# Switches.net
KiCad netlist of a schematic drawn in Altium Designer
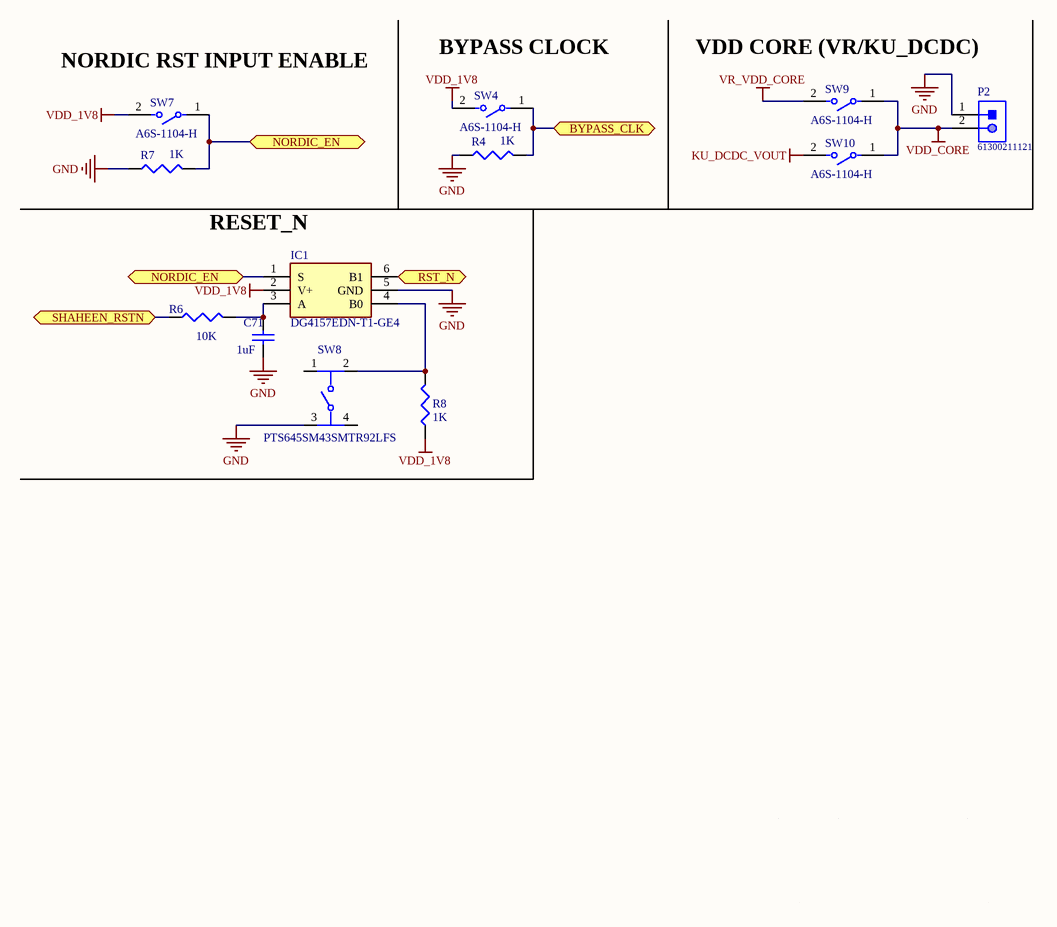
[diagram p0: Switches.SchDoc]

(export (version "E")
  (design (tool "Eeschema 10.0.6"))
  (components
    (comp (ref "C71")
      (value "1uF")
      (footprint "0603")
      (description "Capacitor")
      (fields (field (name "Comment") "Cap") (field (name "PUBLISHER") "Altium Limited"))
      (libsource (lib "Miscellaneous Devices") (part "Cap"))
    )
    (comp (ref "IC1")
      (value "DG4157EDN-T1-GE4")
      (footprint "SON35P100X100X38-6N")
      (description "Integrated Circuit")
      (fields (field (name "MOUSER2 PART NUMBER") "78-DG4157EDN-T1-GE4"))
      (libsource (lib "DG4157EDN-T1-GE4") (part "DG4157EDN-T1-GE4"))
    )
    (comp (ref "P2")
      (value "61300211121")
      (footprint "61300211121")
      (description "THT Vertical Pin Header WR-PHD, Pitch 2.54 mm, Single Row, 2 pins")
      (fields (field (name "MANUFACTURER") "Wurth Elektronik") (field (name "PUBLISHER") "WurthElektronik"))
      (libsource (lib "Altium Content Vault") (part "WE-CN-1P-M-R2"))
    )
    (comp (ref "R4")
      (value "1K")
      (footprint "J1-0603")
      (description "Resistor")
      (fields (field (name "Comment") "0R") (field (name "PUBLISHER") "Altium Limited"))
      (libsource (lib "Miscellaneous Devices") (part "Res3"))
    )
    (comp (ref "R6")
      (value "10K")
      (footprint "J1-0603")
      (description "Resistor")
      (fields (field (name "Comment") "0R") (field (name "PUBLISHER") "Altium Limited"))
      (libsource (lib "Miscellaneous Devices") (part "Res3"))
    )
    (comp (ref "R7")
      (value "1K")
      (footprint "J1-0603")
      (description "Resistor")
      (fields (field (name "Comment") "0R") (field (name "PUBLISHER") "Altium Limited"))
      (libsource (lib "Miscellaneous Devices") (part "Res3"))
    )
    (comp (ref "R8")
      (value "1K")
      (footprint "J1-0603")
      (description "Resistor")
      (fields (field (name "Comment") "0R") (field (name "PUBLISHER") "Altium Limited"))
      (libsource (lib "Miscellaneous Devices") (part "Res3"))
    )
    (comp (ref "SW4")
      (value "A6S-1104-H")
      (footprint "FP-A6S-1104-H-MFG")
      (description "SWITCH SLIDE DIP SPST 25MA 24V")
      (fields
        (field (name "MANUFACTURER") "Omron Electronics Inc-EMC Div")
        (field (name "OCTOPART") "https://octopart.com/a6s-1104-h-omron-55410938")
      )
      (libsource (lib "Altium Content Vault") (part "bb27bde45df87f1f469753f287ef5ae"))
    )
    (comp (ref "SW7")
      (value "A6S-1104-H")
      (footprint "FP-A6S-1104-H-MFG")
      (description "SWITCH SLIDE DIP SPST 25MA 24V")
      (fields
        (field (name "MANUFACTURER") "Omron Electronics Inc-EMC Div")
        (field (name "OCTOPART") "https://octopart.com/a6s-1104-h-omron-55410938")
      )
      (libsource (lib "Altium Content Vault") (part "bb27bde45df87f1f469753f287ef5ae"))
    )
    (comp (ref "SW8")
      (value "PTS645SM43SMTR92LFS")
      (footprint "FP-PTS645SM43SMTR92LFS-MFG")
      (description "SWITCH TACTILE SPST-NO 0.05A 12V")
      (libsource (lib "Altium Content Vault") (part "1adf0dd01260c80cf25a44bfd6b99ba"))
    )
    (comp (ref "SW9")
      (value "A6S-1104-H")
      (footprint "FP-A6S-1104-H-MFG")
      (description "SWITCH SLIDE DIP SPST 25MA 24V")
      (fields
        (field (name "MANUFACTURER") "Omron Electronics Inc-EMC Div")
        (field (name "OCTOPART") "https://octopart.com/a6s-1104-h-omron-55410938")
      )
      (libsource (lib "Altium Content Vault") (part "bb27bde45df87f1f469753f287ef5ae"))
    )
    (comp (ref "SW10")
      (value "A6S-1104-H")
      (footprint "FP-A6S-1104-H-MFG")
      (description "SWITCH SLIDE DIP SPST 25MA 24V")
      (fields
        (field (name "MANUFACTURER") "Omron Electronics Inc-EMC Div")
        (field (name "OCTOPART") "https://octopart.com/a6s-1104-h-omron-55410938")
      )
      (libsource (lib "Altium Content Vault") (part "bb27bde45df87f1f469753f287ef5ae"))
    )
  )
  (nets
    (net (code "1") (name "/BYPASS_CLK") (class "Default")
      (node (ref "R4") (pin "1") (pinfunction "1_1") (pintype "passive"))
      (node (ref "SW4") (pin "1") (pinfunction "1_1") (pintype "passive"))
    )
    (net (code "2") (name "/NORDIC_EN") (class "Default")
      (node (ref "IC1") (pin "1") (pinfunction "S_1") (pintype "passive"))
      (node (ref "R7") (pin "1") (pinfunction "1_1") (pintype "passive"))
      (node (ref "SW7") (pin "1") (pinfunction "1_1") (pintype "passive"))
    )
    (net (code "3") (name "/RST_N") (class "Default")
      (node (ref "IC1") (pin "6") (pinfunction "B1_6") (pintype "passive"))
    )
    (net (code "4") (name "/SHAHEEN_RSTN") (class "Default")
      (node (ref "R6") (pin "2") (pinfunction "2_2") (pintype "passive"))
    )
    (net (code "5") (name "GND") (class "Default")
      (node (ref "C71") (pin "2") (pinfunction "2_2") (pintype "passive"))
      (node (ref "IC1") (pin "5") (pinfunction "GND_5") (pintype "passive"))
      (node (ref "P2") (pin "1") (pinfunction "1_1") (pintype "passive"))
      (node (ref "R4") (pin "2") (pinfunction "2_2") (pintype "passive"))
      (node (ref "R7") (pin "2") (pinfunction "2_2") (pintype "passive"))
      (node (ref "SW8") (pin "3") (pinfunction "3_3") (pintype "passive"))
    )
    (net (code "6") (name "KU_DCDC_VOUT") (class "Default")
      (node (ref "SW10") (pin "2") (pinfunction "2_2") (pintype "passive"))
    )
    (net (code "7") (name "Net-(IC1-A)") (class "Default")
      (node (ref "C71") (pin "1") (pinfunction "1_1") (pintype "passive"))
      (node (ref "IC1") (pin "3") (pinfunction "A_3") (pintype "passive"))
      (node (ref "R6") (pin "1") (pinfunction "1_1") (pintype "passive"))
    )
    (net (code "8") (name "Net-(IC1-B0)") (class "Default")
      (node (ref "IC1") (pin "4") (pinfunction "B0_4") (pintype "passive"))
      (node (ref "R8") (pin "1") (pinfunction "1_1") (pintype "passive"))
      (node (ref "SW8") (pin "2") (pinfunction "2_2") (pintype "passive"))
    )
    (net (code "9") (name "VDD_1V8") (class "Default")
      (node (ref "IC1") (pin "2") (pinfunction "V+_2") (pintype "passive"))
      (node (ref "R8") (pin "2") (pinfunction "2_2") (pintype "passive"))
      (node (ref "SW4") (pin "2") (pinfunction "2_2") (pintype "passive"))
      (node (ref "SW7") (pin "2") (pinfunction "2_2") (pintype "passive"))
    )
    (net (code "10") (name "VDD_CORE") (class "Default")
      (node (ref "P2") (pin "2") (pinfunction "2_2") (pintype "passive"))
      (node (ref "SW10") (pin "1") (pinfunction "1_1") (pintype "passive"))
      (node (ref "SW9") (pin "1") (pinfunction "1_1") (pintype "passive"))
    )
    (net (code "11") (name "VR_VDD_CORE") (class "Default")
      (node (ref "SW9") (pin "2") (pinfunction "2_2") (pintype "passive"))
    )
    (net (code "12") (name "unconnected-(SW8-Pad1)") (class "Default")
      (node (ref "SW8") (pin "1") (pinfunction "1_1") (pintype "passive"))
    )
    (net (code "13") (name "unconnected-(SW8-Pad4)") (class "Default")
      (node (ref "SW8") (pin "4") (pinfunction "4_4") (pintype "passive"))
    )
  )
)
